# delta-sigma_modulator.net
KiCad netlist of a schematic drawn in Altium Designer
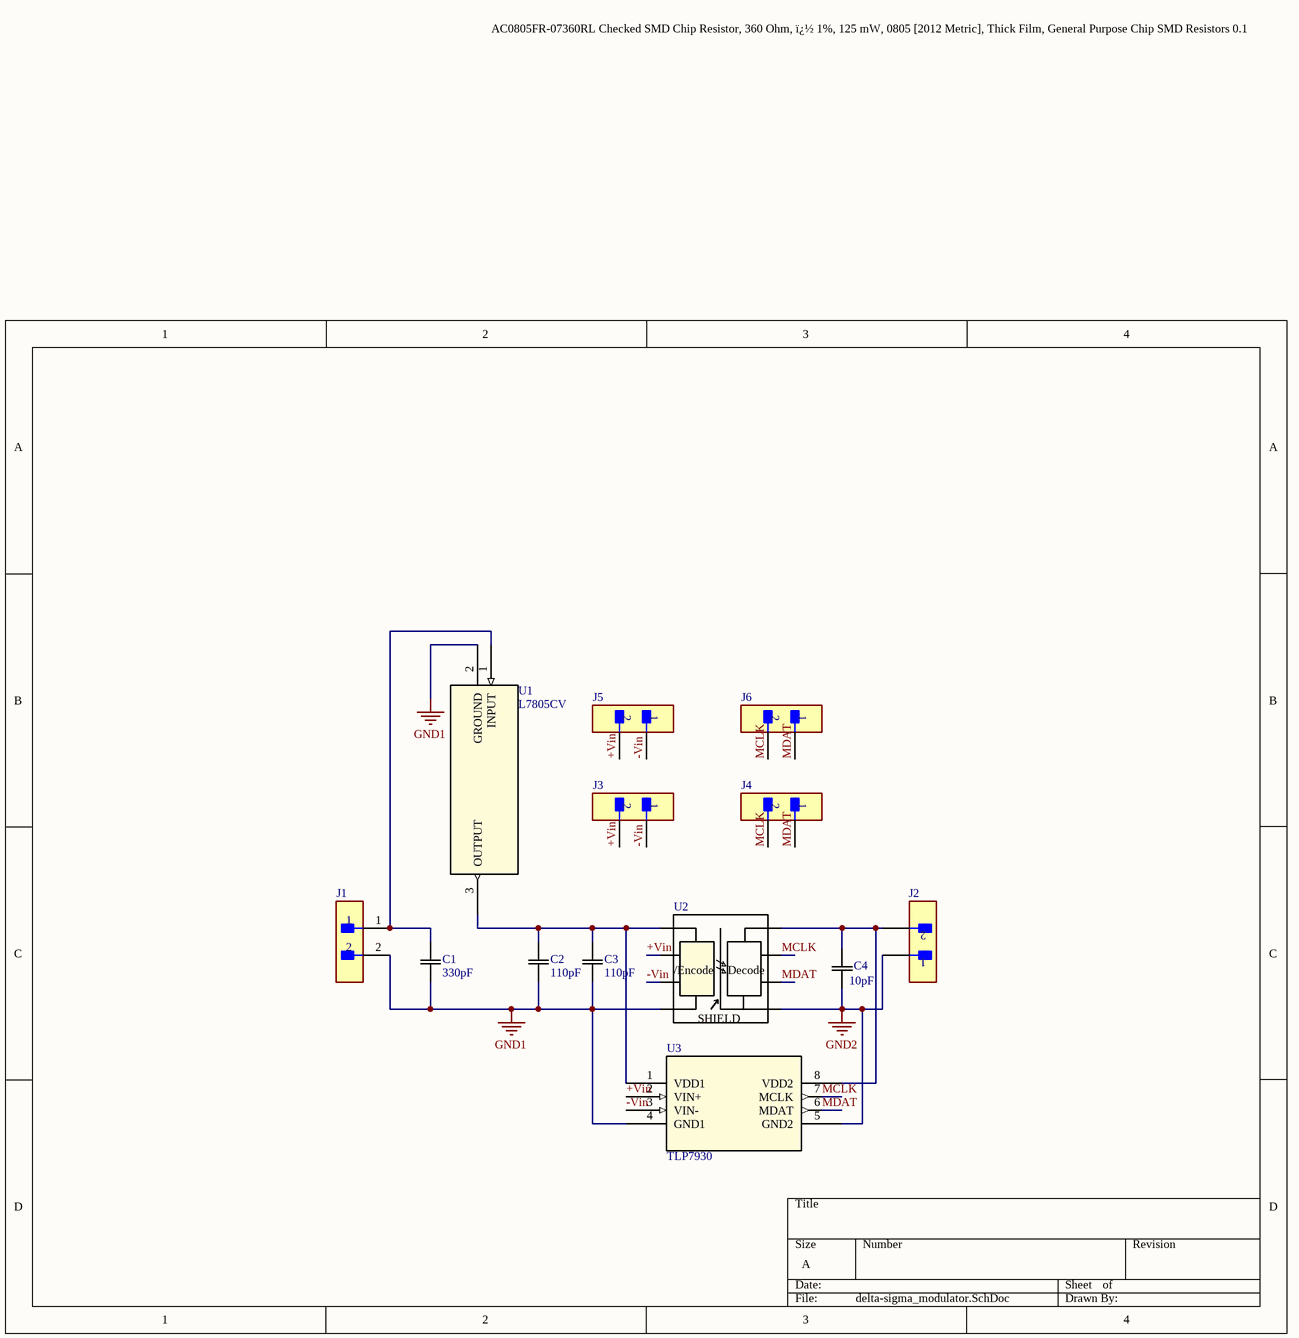
[diagram p0: delta-sigma_modulator.SchDoc]

(export (version "E")
  (design (tool "Eeschema 10.0.6"))
  (components
    (comp (ref "C1")
      (value "330pF")
      (footprint "CAP_FG28_TDK")
      (description "No Description Available")
      (libsource (lib "Schlib1") (part "FG28C0G1H331JNT06"))
    )
    (comp (ref "C2")
      (value "110pF")
      (footprint "CAP_FG28_TDK")
      (description "No Description Available")
      (libsource (lib "Schlib1") (part "FG28C0G1H100DNT06"))
    )
    (comp (ref "C3")
      (value "110pF")
      (footprint "CAP_FG28_TDK")
      (description "No Description Available")
      (libsource (lib "Schlib1") (part "FG28C0G1H100DNT06"))
    )
    (comp (ref "C4")
      (value "10pF")
      (footprint "CAP_C322C511_MR_KEM")
      (description "No Description Available")
      (libsource (lib "Schlib1") (part "C322C111JDG5TA"))
    )
    (comp (ref "J1")
      (value "M20-9990246")
      (footprint "FP-M20-9990246-MFG")
      (description "CONN HEADER VERT 2POS 2.54MM")
      (fields
        (field (name "OCTOPART") "https://octopart.com/m20-9990246-harwin-2590635")
        (field (name "MANUFACTURER") "Harwin")
      )
      (libsource (lib "") (part "3bc925449376181038e59eaffc5286c_2"))
    )
    (comp (ref "J2")
      (value "M20-9990246")
      (footprint "FP-M20-9990246-MFG")
      (description "CONN HEADER VERT 2POS 2.54MM")
      (fields
        (field (name "OCTOPART") "https://octopart.com/m20-9990246-harwin-2590635")
        (field (name "MANUFACTURER") "Harwin")
      )
      (libsource (lib "") (part "3bc925449376181038e59eaffc5286c_1"))
    )
    (comp (ref "J3")
      (value "M20-9990246")
      (footprint "FP-M20-9990246-MFG")
      (description "CONN HEADER VERT 2POS 2.54MM")
      (fields
        (field (name "OCTOPART") "https://octopart.com/m20-9990246-harwin-2590635")
        (field (name "MANUFACTURER") "Harwin")
      )
      (libsource (lib "Altium Content Vault") (part "3bc925449376181038e59eaffc5286c"))
    )
    (comp (ref "J4")
      (value "M20-9990246")
      (footprint "FP-M20-9990246-MFG")
      (description "CONN HEADER VERT 2POS 2.54MM")
      (fields
        (field (name "OCTOPART") "https://octopart.com/m20-9990246-harwin-2590635")
        (field (name "MANUFACTURER") "Harwin")
      )
      (libsource (lib "Altium Content Vault") (part "3bc925449376181038e59eaffc5286c"))
    )
    (comp (ref "J5")
      (value "M20-9990246")
      (footprint "FP-M20-9990246-MFG")
      (description "CONN HEADER VERT 2POS 2.54MM")
      (fields
        (field (name "OCTOPART") "https://octopart.com/m20-9990246-harwin-2590635")
        (field (name "MANUFACTURER") "Harwin")
      )
      (libsource (lib "Altium Content Vault") (part "3bc925449376181038e59eaffc5286c"))
    )
    (comp (ref "J6")
      (value "M20-9990246")
      (footprint "FP-M20-9990246-MFG")
      (description "CONN HEADER VERT 2POS 2.54MM")
      (fields
        (field (name "OCTOPART") "https://octopart.com/m20-9990246-harwin-2590635")
        (field (name "MANUFACTURER") "Harwin")
      )
      (libsource (lib "Altium Content Vault") (part "3bc925449376181038e59eaffc5286c"))
    )
    (comp (ref "U1")
      (value "L7805CV")
      (footprint "TO-220_STM")
      (description "Linear Voltage Regulator, Fixed, Positive Output, 35 V, 5 V, 1.5 A, 3 Pins, TO-220")
      (fields (field (name "MANUFACTURER") "STMicroelectronics") (field (name "TOLERANCE") "5%"))
      (libsource (lib "Schlib1") (part "L7805CV"))
    )
    (comp (ref "U2")
      (value "TLP7830TP4,E")
      (footprint "SO8L_TOS")
      (description "Isolation Amplifier Single 5000Vrms 5V 8-Pin SOIC T/R")
      (fields
        (field (name "MANUFACTURER") "Toshiba")
        (field (name "MANUFACTURER PART NUMBER") "TLP7830(TP4,E")
      )
      (libsource (lib "Schlib1") (part "TLP7830TP4,E"))
    )
    (comp (ref "U3")
      (value "TLP7930")
      (footprint "DIP8_TOS")
      (description "No Description Available")
      (libsource (lib "Schlib1") (part "TLP7930"))
    )
  )
  (nets
    (net (code "1") (name "/+Vin") (class "Default")
      (node (ref "J3") (pin "2") (pinfunction "2_2") (pintype "passive"))
      (node (ref "J5") (pin "2") (pinfunction "2_2") (pintype "passive"))
      (node (ref "U2") (pin "2") (pinfunction "2_2") (pintype "passive"))
      (node (ref "U3") (pin "2") (pinfunction "VIN+_2") (pintype "input"))
    )
    (net (code "2") (name "/-Vin") (class "Default")
      (node (ref "J3") (pin "1") (pinfunction "1_1") (pintype "passive"))
      (node (ref "J5") (pin "1") (pinfunction "1_1") (pintype "passive"))
      (node (ref "U2") (pin "3") (pinfunction "3_3") (pintype "passive"))
      (node (ref "U3") (pin "3") (pinfunction "VIN-_3") (pintype "input"))
    )
    (net (code "3") (name "/MCLK") (class "Default")
      (node (ref "J4") (pin "2") (pinfunction "2_2") (pintype "passive"))
      (node (ref "J6") (pin "2") (pinfunction "2_2") (pintype "passive"))
      (node (ref "U2") (pin "7") (pinfunction "7_7") (pintype "passive"))
      (node (ref "U3") (pin "7") (pinfunction "MCLK_7") (pintype "output"))
    )
    (net (code "4") (name "/MDAT") (class "Default")
      (node (ref "J4") (pin "1") (pinfunction "1_1") (pintype "passive"))
      (node (ref "J6") (pin "1") (pinfunction "1_1") (pintype "passive"))
      (node (ref "U2") (pin "6") (pinfunction "6_6") (pintype "passive"))
      (node (ref "U3") (pin "6") (pinfunction "MDAT_6") (pintype "output"))
    )
    (net (code "5") (name "GND1") (class "Default")
      (node (ref "C1") (pin "1") (pinfunction "1_1") (pintype "passive"))
      (node (ref "C2") (pin "1") (pinfunction "1_1") (pintype "passive"))
      (node (ref "C3") (pin "1") (pinfunction "1_1") (pintype "passive"))
      (node (ref "J1") (pin "2") (pinfunction "1_2") (pintype "passive"))
      (node (ref "U1") (pin "2") (pinfunction "GROUND_2") (pintype "power_in"))
      (node (ref "U2") (pin "4") (pinfunction "4_4") (pintype "passive"))
      (node (ref "U3") (pin "4") (pinfunction "GND1_4") (pintype "power_in"))
    )
    (net (code "6") (name "GND2") (class "Default")
      (node (ref "C4") (pin "1") (pinfunction "1_1") (pintype "passive"))
      (node (ref "J2") (pin "2") (pinfunction "2_2") (pintype "passive"))
      (node (ref "U2") (pin "5") (pinfunction "5_5") (pintype "passive"))
      (node (ref "U3") (pin "5") (pinfunction "GND2_5") (pintype "power_in"))
    )
    (net (code "7") (name "Net-(J1-2)") (class "Default")
      (node (ref "C1") (pin "2") (pinfunction "2_2") (pintype "passive"))
      (node (ref "J1") (pin "1") (pinfunction "2_1") (pintype "passive"))
      (node (ref "U1") (pin "1") (pinfunction "INPUT_1") (pintype "input"))
    )
    (net (code "8") (name "Net-(U1-OUTPUT)") (class "Default")
      (node (ref "C2") (pin "2") (pinfunction "2_2") (pintype "passive"))
      (node (ref "C3") (pin "2") (pinfunction "2_2") (pintype "passive"))
      (node (ref "U1") (pin "3") (pinfunction "OUTPUT_3") (pintype "output"))
      (node (ref "U2") (pin "1") (pinfunction "1_1") (pintype "passive"))
      (node (ref "U3") (pin "1") (pinfunction "VDD1_1") (pintype "power_in"))
    )
    (net (code "9") (name "Net-(U3-VDD2)") (class "Default")
      (node (ref "C4") (pin "2") (pinfunction "2_2") (pintype "passive"))
      (node (ref "J2") (pin "1") (pinfunction "1_1") (pintype "passive"))
      (node (ref "U2") (pin "8") (pinfunction "8_8") (pintype "passive"))
      (node (ref "U3") (pin "8") (pinfunction "VDD2_8") (pintype "power_in"))
    )
  )
)
